# MCU.net
KiCad netlist of a schematic drawn in Altium Designer
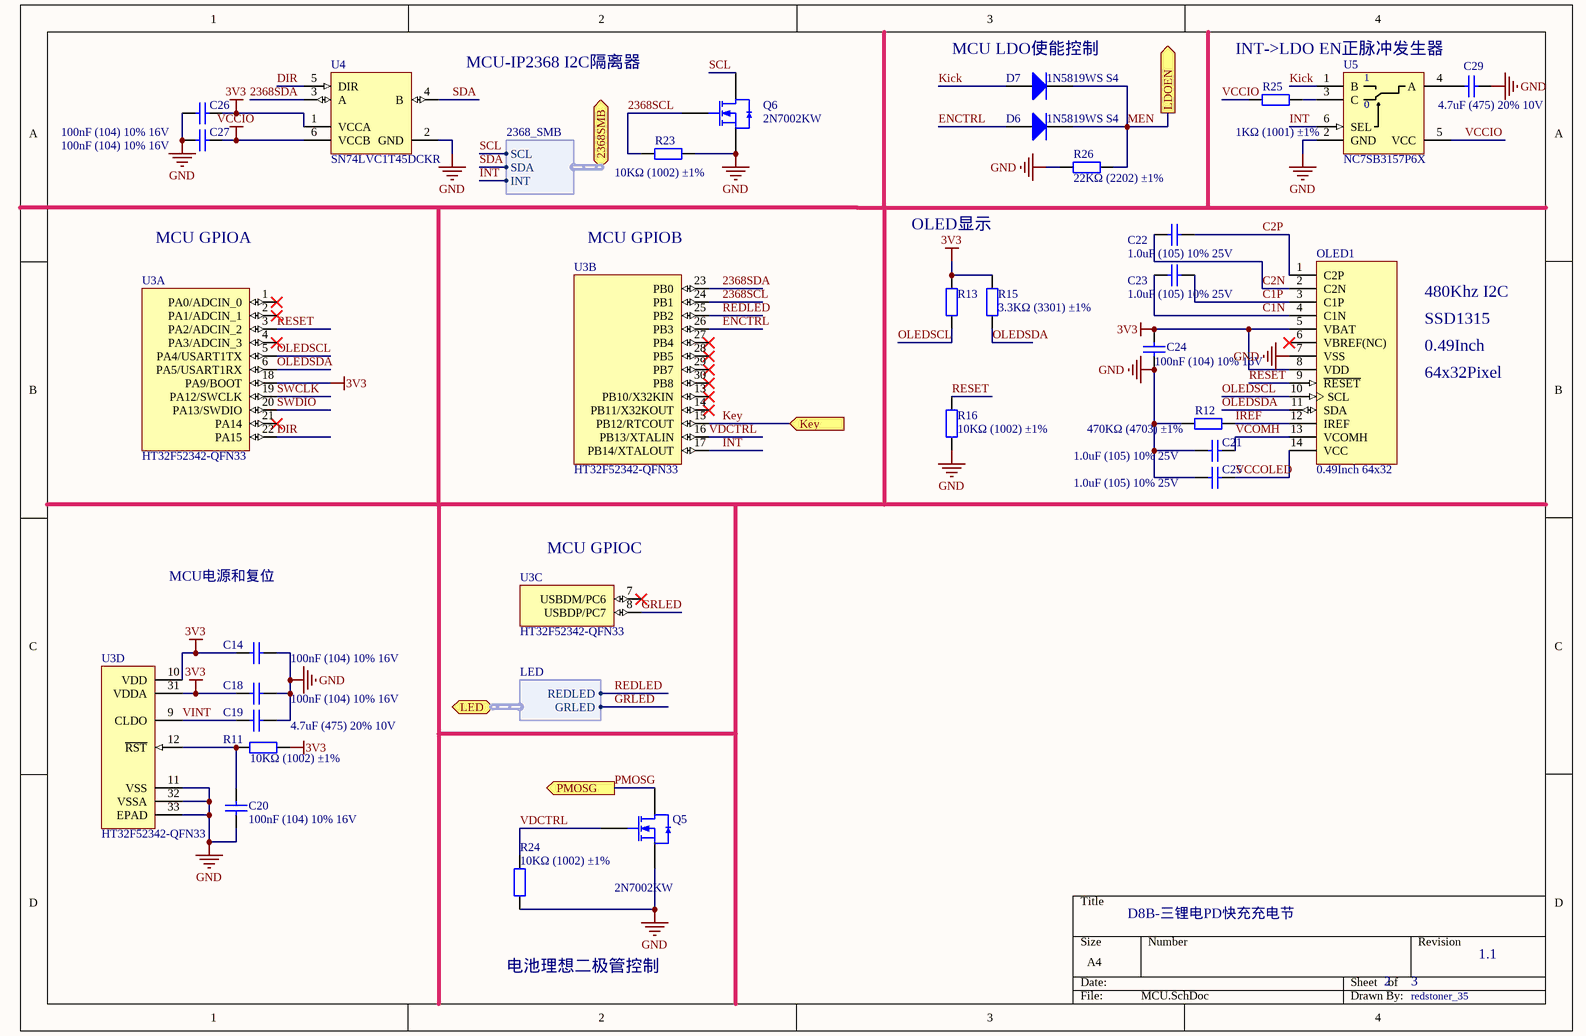
[diagram p0: MCU.SchDoc]

(export (version "E")
  (design (tool "Eeschema 10.0.6"))
  (components
    (comp (ref "C14")
      (value "100nF (104) 10% 16V")
      (footprint "0402_C")
      (description "贴片电容")
      (libsource (lib "Miscellaneous Devices LC") (part "0402 100nF (104) 10% 16V"))
    )
    (comp (ref "C18")
      (value "100nF (104) 10% 16V")
      (footprint "0402_C")
      (description "贴片电容")
      (libsource (lib "Miscellaneous Devices LC") (part "0402 100nF (104) 10% 16V"))
    )
    (comp (ref "C19")
      (value "4.7uF (475) 20% 10V")
      (footprint "0402_C")
      (description "贴片电容")
      (libsource (lib "Miscellaneous Devices LC") (part "0402 4.7uF (475) 20% 10V"))
    )
    (comp (ref "C20")
      (value "100nF (104) 10% 16V")
      (footprint "0402_C")
      (description "贴片电容")
      (libsource (lib "Miscellaneous Devices LC") (part "0402 100nF (104) 10% 16V"))
    )
    (comp (ref "C21")
      (value "1.0uF (105) 10% 25V")
      (footprint "0402_C")
      (description "贴片电容")
      (libsource (lib "Miscellaneous Devices LC") (part "0402 1.0uF (105) 10% 25V"))
    )
    (comp (ref "C22")
      (value "1.0uF (105) 10% 25V")
      (footprint "0402_C")
      (description "贴片电容")
      (libsource (lib "Miscellaneous Devices LC") (part "0402 1.0uF (105) 10% 25V"))
    )
    (comp (ref "C23")
      (value "1.0uF (105) 10% 25V")
      (footprint "0402_C")
      (description "贴片电容")
      (libsource (lib "Miscellaneous Devices LC") (part "0402 1.0uF (105) 10% 25V"))
    )
    (comp (ref "C24")
      (value "100nF (104) 10% 16V")
      (footprint "0402_C")
      (description "贴片电容")
      (libsource (lib "Miscellaneous Devices LC") (part "0402 100nF (104) 10% 16V"))
    )
    (comp (ref "C25")
      (value "1.0uF (105) 10% 25V")
      (footprint "0402_C")
      (description "贴片电容")
      (libsource (lib "Miscellaneous Devices LC") (part "0402 1.0uF (105) 10% 25V"))
    )
    (comp (ref "C26")
      (value "100nF (104) 10% 16V")
      (footprint "0402_C")
      (description "贴片电容")
      (libsource (lib "Miscellaneous Devices LC") (part "0402 100nF (104) 10% 16V"))
    )
    (comp (ref "C27")
      (value "100nF (104) 10% 16V")
      (footprint "0402_C")
      (description "贴片电容")
      (libsource (lib "Miscellaneous Devices LC") (part "0402 100nF (104) 10% 16V"))
    )
    (comp (ref "C29")
      (value "4.7uF (475) 20% 10V")
      (footprint "0402_C")
      (description "贴片电容")
      (libsource (lib "Miscellaneous Devices LC") (part "0402 4.7uF (475) 20% 10V"))
    )
    (comp (ref "D6")
      (value "1N5819WS S4")
      (footprint "SOD-323")
      (description "二极管")
      (libsource (lib "Miscellaneous Devices LC") (part "SOD-323 1N4148WS T4"))
    )
    (comp (ref "D7")
      (value "1N5819WS S4")
      (footprint "SOD-323")
      (description "二极管")
      (libsource (lib "Miscellaneous Devices LC") (part "SOD-323 1N4148WS T4"))
    )
    (comp (ref "OLED1")
      (value "0.49Inch 64x32")
      (footprint "OLED-0.49Inch")
      (description "0.49英寸OLED 64*32像素")
      (libsource (lib "custom") (part "0.49Inch OLED"))
    )
    (comp (ref "Q5")
      (value "2N7002KW")
      (footprint "SC70-3")
      (description "MOS(场效应管)")
      (libsource (lib "Miscellaneous Devices LC") (part "2N7002 7002"))
    )
    (comp (ref "Q6")
      (value "2N7002KW")
      (footprint "SC70-3")
      (description "MOS(场效应管)")
      (libsource (lib "Miscellaneous Devices LC") (part "2N7002 7002"))
    )
    (comp (ref "R11")
      (value "10KΩ (1002) ±1%")
      (footprint "0402_R")
      (description "贴片电阻")
      (libsource (lib "") (part "0402 10KΩ (1002) 1%_1"))
    )
    (comp (ref "R12")
      (value "470KΩ (4703) ±1%")
      (footprint "0402_R")
      (description "贴片电阻")
      (libsource (lib "Miscellaneous Devices LC") (part "0402 470KΩ (4703) 1%"))
    )
    (comp (ref "R13")
      (value "3.3KΩ (3301) ±1%")
      (footprint "0402_R")
      (description "贴片电阻")
      (libsource (lib "Miscellaneous Devices LC") (part "0402 3.3KΩ (3301) 1%"))
    )
    (comp (ref "R15")
      (value "3.3KΩ (3301) ±1%")
      (footprint "0402_R")
      (description "贴片电阻")
      (libsource (lib "Miscellaneous Devices LC") (part "0402 3.3KΩ (3301) 1%"))
    )
    (comp (ref "R16")
      (value "10KΩ (1002) ±1%")
      (footprint "0402_R")
      (description "贴片电阻")
      (libsource (lib "Miscellaneous Devices LC") (part "0402 10KΩ (1002) 1%"))
    )
    (comp (ref "R23")
      (value "10KΩ (1002) ±1%")
      (footprint "0402_R")
      (description "贴片电阻")
      (libsource (lib "") (part "0402 10KΩ (1002) 1%_1"))
    )
    (comp (ref "R24")
      (value "10KΩ (1002) ±1%")
      (footprint "0402_R")
      (description "贴片电阻")
      (libsource (lib "Miscellaneous Devices LC") (part "0402 10KΩ (1002) 1%"))
    )
    (comp (ref "R25")
      (value "1KΩ (1001) ±1%")
      (footprint "0402_R")
      (description "贴片电阻")
      (libsource (lib "Miscellaneous Devices LC") (part "0402 1KΩ (1001) 1%"))
    )
    (comp (ref "R26")
      (value "22KΩ (2202) ±1%")
      (footprint "0402_R")
      (description "贴片电阻")
      (libsource (lib "Miscellaneous Devices LC") (part "0402 22KΩ (2202) 1%"))
    )
    (comp (ref "U3")
      (value "HT32F52342-QFN33")
      (footprint "QFN32-HT32")
      (description "Holtek MCU Cortex M0+ 48MHz 64K ROM 16K RAM")
      (libsource (lib "custom") (part "HT32F52352-QFN"))
    )
    (comp (ref "U4")
      (value "SN74LVC1T45DCKR")
      (footprint "DCK0006A_N")
      (fields
        (field (name "GENERIC PART NUMBER") "SN74LVC1T45")
        (field (name "MANUFACTURER") "Texas Instruments")
      )
      (libsource (lib "TI_Logic_Little_Logic") (part "SN74LVC1T45DCKR"))
    )
    (comp (ref "U5")
      (value "NC7SB3157P6X")
      (footprint "SC70-6")
      (description "Low-Voltage Analog Switch SPDT,1.8-5V Power")
      (libsource (lib "custom") (part "NC7SB3157P6X"))
    )
  )
  (nets
    (net (code "3") (name "/2368SCL") (class "Default")
      (node (ref "Q6") (pin "1") (pinfunction "G_1") (pintype "passive"))
      (node (ref "R23") (pin "1") (pinfunction "1_1") (pintype "passive"))
      (node (ref "U3") (pin "24") (pinfunction "PB1_24") (pintype "bidirectional"))
    )
    (net (code "4") (name "/2368SDA") (class "Default")
      (node (ref "U3") (pin "23") (pinfunction "PB0_23") (pintype "bidirectional"))
      (node (ref "U4") (pin "3") (pinfunction "A_3") (pintype "bidirectional"))
    )
    (net (code "5") (name "/C1N") (class "Default")
      (node (ref "C23") (pin "2") (pinfunction "2_2") (pintype "passive"))
      (node (ref "OLED1") (pin "4") (pinfunction "C1N_4") (pintype "passive"))
    )
    (net (code "6") (name "/C1P") (class "Default")
      (node (ref "C23") (pin "1") (pinfunction "1_1") (pintype "passive"))
      (node (ref "OLED1") (pin "3") (pinfunction "C1P_3") (pintype "passive"))
    )
    (net (code "7") (name "/C2N") (class "Default")
      (node (ref "C22") (pin "2") (pinfunction "2_2") (pintype "passive"))
      (node (ref "OLED1") (pin "2") (pinfunction "C2N_2") (pintype "passive"))
    )
    (net (code "8") (name "/C2P") (class "Default")
      (node (ref "C22") (pin "1") (pinfunction "1_1") (pintype "passive"))
      (node (ref "OLED1") (pin "1") (pinfunction "C2P_1") (pintype "passive"))
    )
    (net (code "9") (name "/DIR") (class "Default")
      (node (ref "U3") (pin "22") (pinfunction "PA15_22") (pintype "bidirectional"))
      (node (ref "U4") (pin "5") (pinfunction "DIR_5") (pintype "input"))
    )
    (net (code "10") (name "/ENCTRL") (class "Default")
      (node (ref "D6") (pin "1") (pinfunction "A_1") (pintype "passive"))
      (node (ref "U3") (pin "26") (pinfunction "PB3_26") (pintype "bidirectional"))
    )
    (net (code "11") (name "/GRLED") (class "Default")
      (node (ref "U3") (pin "8") (pinfunction "USBDP/PC7_8") (pintype "bidirectional"))
    )
    (net (code "12") (name "/INT") (class "Default")
      (node (ref "U3") (pin "17") (pinfunction "PB14/XTALOUT_17") (pintype "bidirectional"))
      (node (ref "U5") (pin "6") (pinfunction "SEL_6") (pintype "input"))
    )
    (net (code "13") (name "/IREF") (class "Default")
      (node (ref "OLED1") (pin "12") (pinfunction "IREF_12") (pintype "power_in"))
      (node (ref "R12") (pin "1") (pinfunction "1_1") (pintype "passive"))
    )
    (net (code "14") (name "/Key") (class "Default")
      (node (ref "U3") (pin "15") (pinfunction "PB12/RTCOUT_15") (pintype "bidirectional"))
    )
    (net (code "15") (name "/Kick") (class "Default")
      (node (ref "D7") (pin "1") (pinfunction "A_1") (pintype "passive"))
      (node (ref "U5") (pin "1") (pinfunction "B_1") (pintype "passive"))
    )
    (net (code "16") (name "/MEN") (class "Default")
      (node (ref "D6") (pin "2") (pinfunction "K_2") (pintype "passive"))
      (node (ref "D7") (pin "2") (pinfunction "K_2") (pintype "passive"))
      (node (ref "R26") (pin "2") (pinfunction "2_2") (pintype "passive"))
    )
    (net (code "17") (name "/OLEDSCL") (class "Default")
      (node (ref "OLED1") (pin "10") (pinfunction "SCL_10") (pintype "input"))
      (node (ref "R13") (pin "1") (pinfunction "1_1") (pintype "passive"))
      (node (ref "U3") (pin "5") (pinfunction "PA4/USART1TX_5") (pintype "bidirectional"))
    )
    (net (code "18") (name "/OLEDSDA") (class "Default")
      (node (ref "OLED1") (pin "11") (pinfunction "SDA_11") (pintype "bidirectional"))
      (node (ref "R15") (pin "1") (pinfunction "1_1") (pintype "passive"))
      (node (ref "U3") (pin "6") (pinfunction "PA5/USART1RX_6") (pintype "bidirectional"))
    )
    (net (code "19") (name "/PMOSG") (class "Default")
      (node (ref "Q5") (pin "3") (pinfunction "D_3") (pintype "passive"))
    )
    (net (code "20") (name "/REDLED") (class "Default")
      (node (ref "U3") (pin "25") (pinfunction "PB2_25") (pintype "bidirectional"))
    )
    (net (code "21") (name "/RESET") (class "Default")
      (node (ref "OLED1") (pin "9") (pinfunction "~{RESET}_9") (pintype "input"))
      (node (ref "R16") (pin "2") (pinfunction "2_2") (pintype "passive"))
      (node (ref "U3") (pin "3") (pinfunction "PA2/ADCIN_2_3") (pintype "bidirectional"))
    )
    (net (code "22") (name "/SCL") (class "Default")
      (node (ref "Q6") (pin "3") (pinfunction "D_3") (pintype "passive"))
    )
    (net (code "23") (name "/SDA") (class "Default")
      (node (ref "U4") (pin "4") (pinfunction "B_4") (pintype "bidirectional"))
    )
    (net (code "24") (name "/SWCLK") (class "Default")
      (node (ref "U3") (pin "19") (pinfunction "PA12/SWCLK_19") (pintype "bidirectional"))
    )
    (net (code "25") (name "/SWDIO") (class "Default")
      (node (ref "U3") (pin "20") (pinfunction "PA13/SWDIO_20") (pintype "bidirectional"))
    )
    (net (code "26") (name "/VCCOLED") (class "Default")
      (node (ref "C25") (pin "2") (pinfunction "2_2") (pintype "passive"))
      (node (ref "OLED1") (pin "14") (pinfunction "VCC_14") (pintype "power_in"))
    )
    (net (code "27") (name "/VCOMH") (class "Default")
      (node (ref "C21") (pin "1") (pinfunction "1_1") (pintype "passive"))
      (node (ref "OLED1") (pin "13") (pinfunction "VCOMH_13") (pintype "power_in"))
    )
    (net (code "28") (name "/VDCTRL") (class "Default")
      (node (ref "Q5") (pin "1") (pinfunction "G_1") (pintype "passive"))
      (node (ref "R24") (pin "2") (pinfunction "2_2") (pintype "passive"))
      (node (ref "U3") (pin "16") (pinfunction "PB13/XTALIN_16") (pintype "bidirectional"))
    )
    (net (code "29") (name "/VINT") (class "Default")
      (node (ref "C19") (pin "1") (pinfunction "1_1") (pintype "passive"))
      (node (ref "U3") (pin "9") (pinfunction "CLDO_9") (pintype "power_in"))
    )
    (net (code "32") (name "3V3") (class "Default")
      (node (ref "C14") (pin "1") (pinfunction "1_1") (pintype "passive"))
      (node (ref "C18") (pin "1") (pinfunction "1_1") (pintype "passive"))
      (node (ref "C24") (pin "2") (pinfunction "2_2") (pintype "passive"))
      (node (ref "C26") (pin "2") (pinfunction "2_2") (pintype "passive"))
      (node (ref "OLED1") (pin "5") (pinfunction "VBAT_5") (pintype "power_in"))
      (node (ref "OLED1") (pin "8") (pinfunction "VDD_8") (pintype "power_in"))
      (node (ref "R11") (pin "2") (pinfunction "2_2") (pintype "passive"))
      (node (ref "R13") (pin "2") (pinfunction "2_2") (pintype "passive"))
      (node (ref "R15") (pin "2") (pinfunction "2_2") (pintype "passive"))
      (node (ref "U3") (pin "10") (pinfunction "VDD_10") (pintype "power_in"))
      (node (ref "U3") (pin "18") (pinfunction "PA9/BOOT_18") (pintype "bidirectional"))
      (node (ref "U3") (pin "31") (pinfunction "VDDA_31") (pintype "power_in"))
      (node (ref "U4") (pin "1") (pinfunction "VCCA_1") (pintype "power_in"))
    )
    (net (code "33") (name "GND") (class "Default")
      (node (ref "C14") (pin "2") (pinfunction "2_2") (pintype "passive"))
      (node (ref "C18") (pin "2") (pinfunction "2_2") (pintype "passive"))
      (node (ref "C19") (pin "2") (pinfunction "2_2") (pintype "passive"))
      (node (ref "C20") (pin "1") (pinfunction "1_1") (pintype "passive"))
      (node (ref "C21") (pin "2") (pinfunction "2_2") (pintype "passive"))
      (node (ref "C24") (pin "1") (pinfunction "1_1") (pintype "passive"))
      (node (ref "C25") (pin "1") (pinfunction "1_1") (pintype "passive"))
      (node (ref "C26") (pin "1") (pinfunction "1_1") (pintype "passive"))
      (node (ref "C27") (pin "1") (pinfunction "1_1") (pintype "passive"))
      (node (ref "C29") (pin "2") (pinfunction "2_2") (pintype "passive"))
      (node (ref "OLED1") (pin "7") (pinfunction "VSS_7") (pintype "power_in"))
      (node (ref "Q5") (pin "2") (pinfunction "S_2") (pintype "passive"))
      (node (ref "Q6") (pin "2") (pinfunction "S_2") (pintype "passive"))
      (node (ref "R12") (pin "2") (pinfunction "2_2") (pintype "passive"))
      (node (ref "R16") (pin "1") (pinfunction "1_1") (pintype "passive"))
      (node (ref "R23") (pin "2") (pinfunction "2_2") (pintype "passive"))
      (node (ref "R24") (pin "1") (pinfunction "1_1") (pintype "passive"))
      (node (ref "R26") (pin "1") (pinfunction "1_1") (pintype "passive"))
      (node (ref "U3") (pin "11") (pinfunction "VSS_11") (pintype "power_in"))
      (node (ref "U3") (pin "32") (pinfunction "VSSA_32") (pintype "power_in"))
      (node (ref "U3") (pin "33") (pinfunction "EPAD_33") (pintype "power_in"))
      (node (ref "U4") (pin "2") (pinfunction "GND_2") (pintype "power_in"))
      (node (ref "U5") (pin "2") (pinfunction "GND_2") (pintype "power_in"))
    )
    (net (code "34") (name "Net-(U3D-~{RST})") (class "Default")
      (node (ref "C20") (pin "2") (pinfunction "2_2") (pintype "passive"))
      (node (ref "R11") (pin "1") (pinfunction "1_1") (pintype "passive"))
      (node (ref "U3") (pin "12") (pinfunction "~{RST}_12") (pintype "input"))
    )
    (net (code "35") (name "Net-(U5-A)") (class "Default")
      (node (ref "C29") (pin "1") (pinfunction "1_1") (pintype "passive"))
      (node (ref "U5") (pin "4") (pinfunction "A_4") (pintype "passive"))
    )
    (net (code "36") (name "Net-(U5-C)") (class "Default")
      (node (ref "R25") (pin "2") (pinfunction "2_2") (pintype "passive"))
      (node (ref "U5") (pin "3") (pinfunction "C_3") (pintype "passive"))
    )
    (net (code "37") (name "VCCIO") (class "Default")
      (node (ref "C27") (pin "2") (pinfunction "2_2") (pintype "passive"))
      (node (ref "R25") (pin "1") (pinfunction "1_1") (pintype "passive"))
      (node (ref "U4") (pin "6") (pinfunction "VCCB_6") (pintype "power_in"))
      (node (ref "U5") (pin "5") (pinfunction "VCC_5") (pintype "power_in"))
    )
    (net (code "38") (name "unconnected-(OLED1-VBREF(NC)-Pad6)") (class "Default")
      (node (ref "OLED1") (pin "6") (pinfunction "VBREF(NC)_6") (pintype "power_in+no_connect"))
    )
    (net (code "39") (name "unconnected-(U3A-PA0{slash}ADCIN_0-Pad1)") (class "Default")
      (node (ref "U3") (pin "1") (pinfunction "PA0/ADCIN_0_1") (pintype "bidirectional+no_connect"))
    )
    (net (code "40") (name "unconnected-(U3A-PA1{slash}ADCIN_1-Pad2)") (class "Default")
      (node (ref "U3") (pin "2") (pinfunction "PA1/ADCIN_1_2") (pintype "bidirectional+no_connect"))
    )
    (net (code "41") (name "unconnected-(U3A-PA3{slash}ADCIN_3-Pad4)") (class "Default")
      (node (ref "U3") (pin "4") (pinfunction "PA3/ADCIN_3_4") (pintype "bidirectional+no_connect"))
    )
    (net (code "42") (name "unconnected-(U3A-PA14-Pad21)") (class "Default")
      (node (ref "U3") (pin "21") (pinfunction "PA14_21") (pintype "bidirectional+no_connect"))
    )
    (net (code "43") (name "unconnected-(U3B-PB4-Pad27)") (class "Default")
      (node (ref "U3") (pin "27") (pinfunction "PB4_27") (pintype "bidirectional+no_connect"))
    )
    (net (code "44") (name "unconnected-(U3B-PB5-Pad28)") (class "Default")
      (node (ref "U3") (pin "28") (pinfunction "PB5_28") (pintype "bidirectional+no_connect"))
    )
    (net (code "45") (name "unconnected-(U3B-PB7-Pad29)") (class "Default")
      (node (ref "U3") (pin "29") (pinfunction "PB7_29") (pintype "bidirectional+no_connect"))
    )
    (net (code "46") (name "unconnected-(U3B-PB8-Pad30)") (class "Default")
      (node (ref "U3") (pin "30") (pinfunction "PB8_30") (pintype "bidirectional+no_connect"))
    )
    (net (code "47") (name "unconnected-(U3B-PB10{slash}X32KIN-Pad13)") (class "Default")
      (node (ref "U3") (pin "13") (pinfunction "PB10/X32KIN_13") (pintype "bidirectional+no_connect"))
    )
    (net (code "48") (name "unconnected-(U3B-PB11{slash}X32KOUT-Pad14)") (class "Default")
      (node (ref "U3") (pin "14") (pinfunction "PB11/X32KOUT_14") (pintype "bidirectional+no_connect"))
    )
    (net (code "49") (name "unconnected-(U3C-USBDM{slash}PC6-Pad7)") (class "Default")
      (node (ref "U3") (pin "7") (pinfunction "USBDM/PC6_7") (pintype "bidirectional+no_connect"))
    )
  )
)
